# LCD_SD.net
KiCad netlist of a schematic drawn in Altium Designer
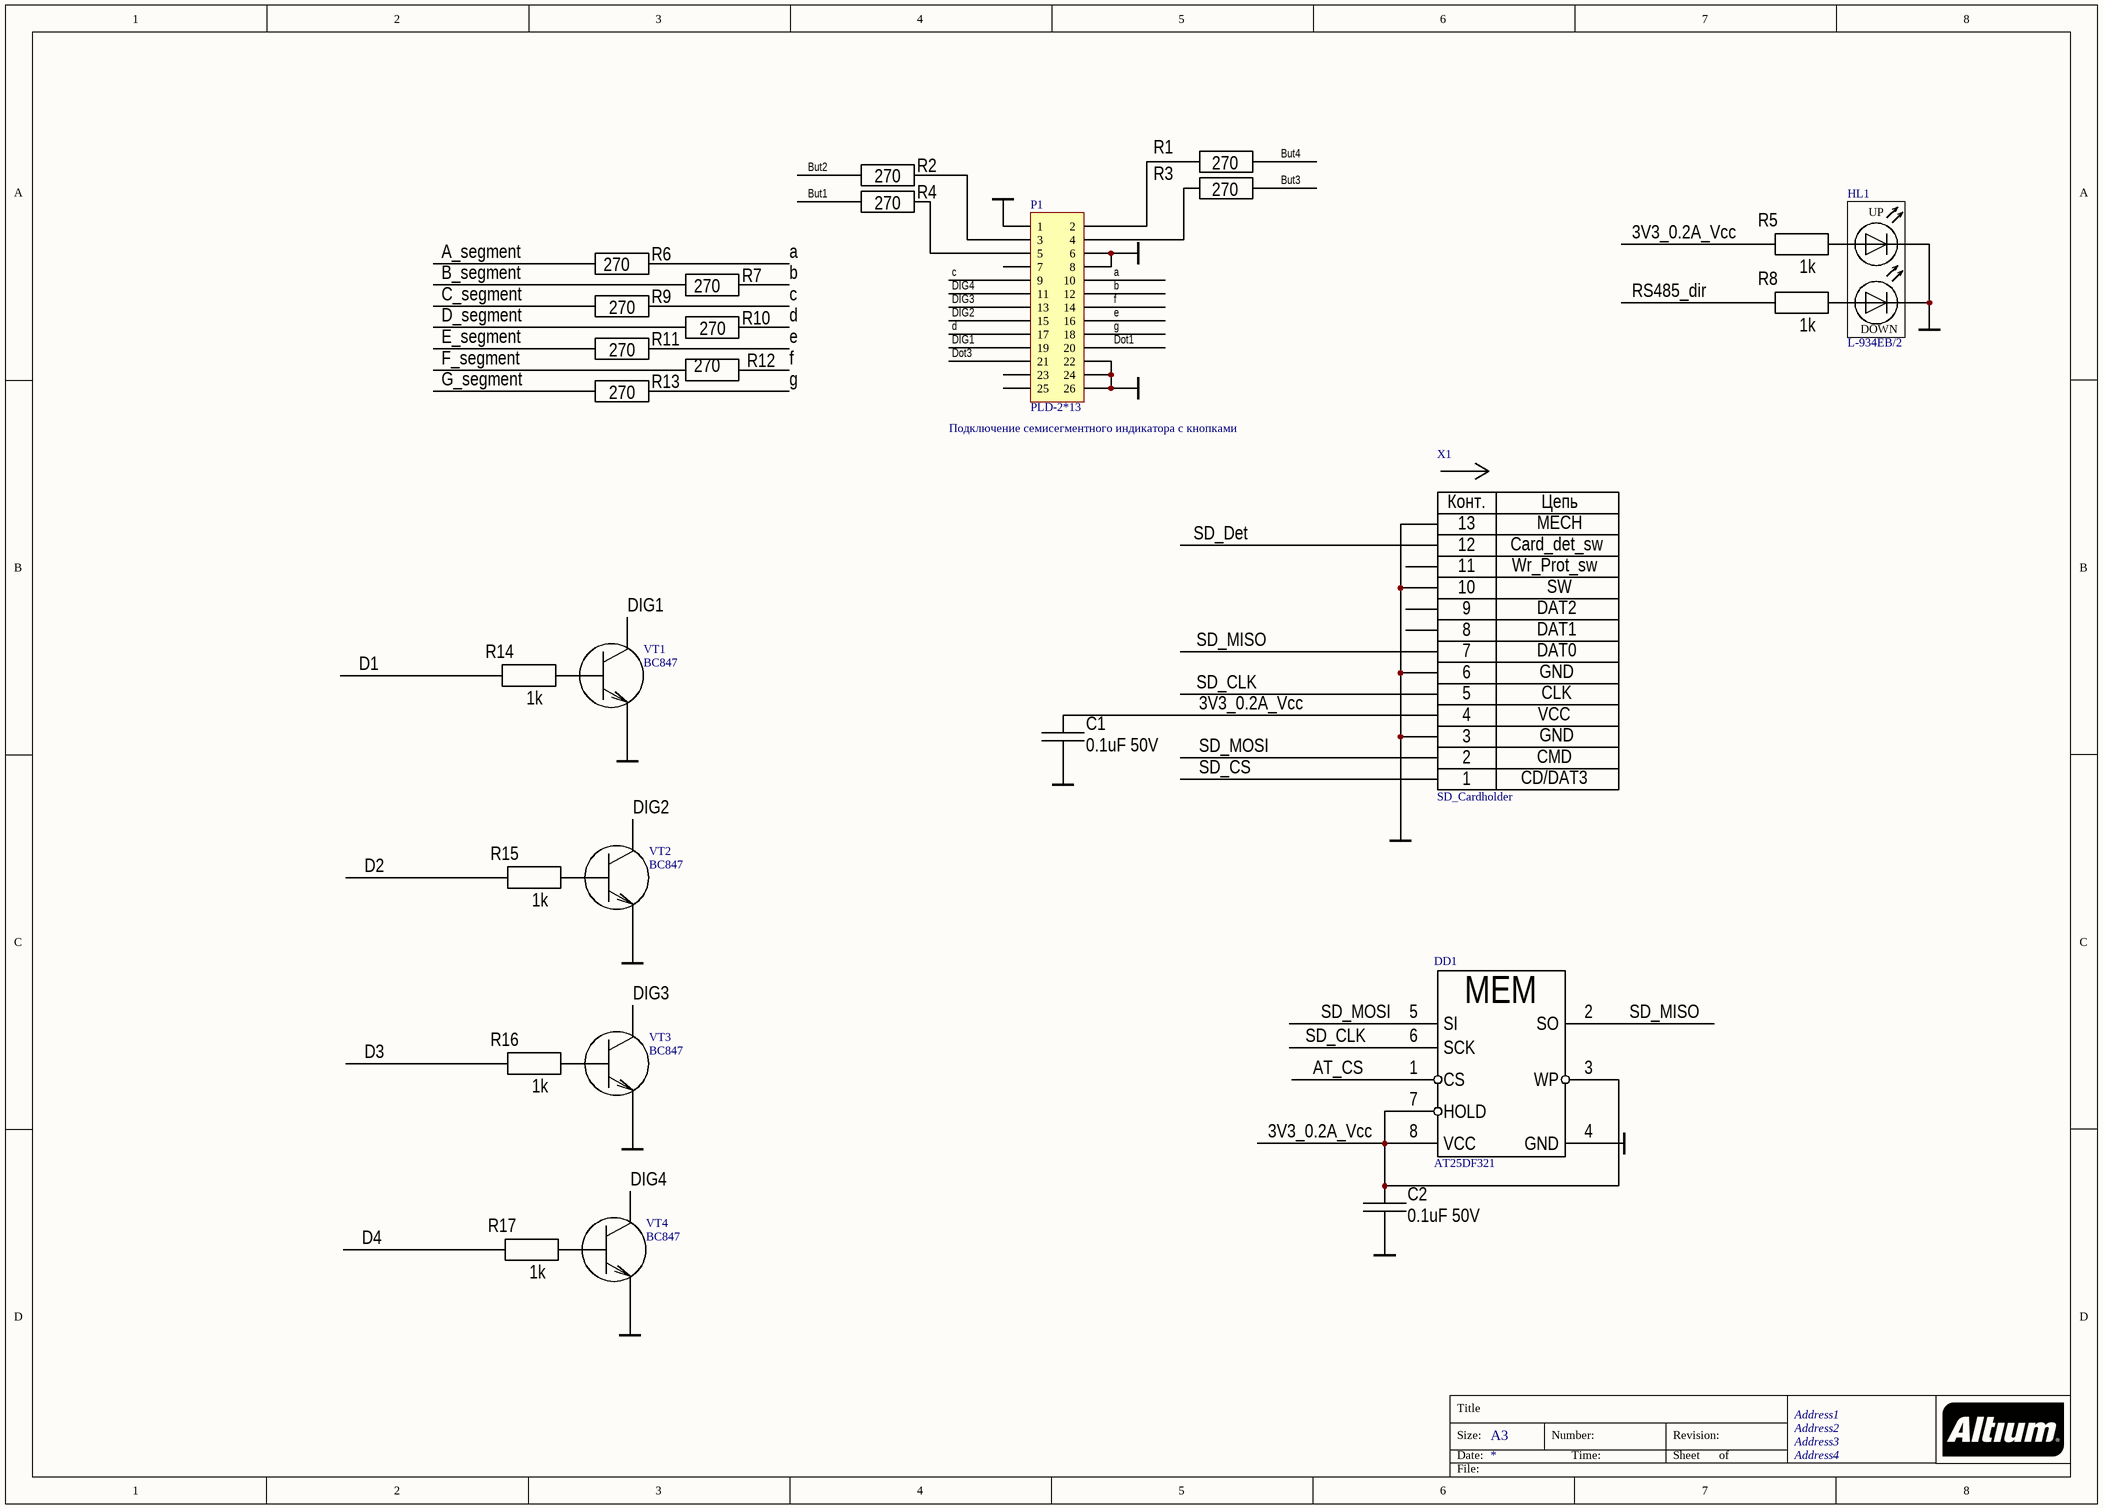
[diagram p0: LCD_SD.SchDoc]

(export (version "E")
  (design (tool "Eeschema 10.0.6"))
  (components
    (comp (ref "C1")
      (value "0.1uF 50V")
      (footprint "0805_CAP")
      (libsource (lib "Integrated_Library_tikhovikt") (part "Cap_np"))
    )
    (comp (ref "C2")
      (value "0.1uF 50V")
      (footprint "0805_CAP")
      (libsource (lib "Integrated_Library_tikhovikt") (part "Cap_np"))
    )
    (comp (ref "DD1")
      (value "AT25DF321")
      (footprint "soic8-200")
      (libsource (lib "Integrated_Library_tikhovikt") (part "AT25DF321"))
    )
    (comp (ref "HL1")
      (value "L-934EB/2")
      (footprint "L-934EB/2")
      (libsource (lib "Integrated_Library_tikhovikt") (part "LEDx2"))
    )
    (comp (ref "P1")
      (value "PLD-2*13")
      (footprint "HDR2X13")
      (description "Header, 13-Pin, Dual row")
      (fields (field (name "DESTINY") "Подключение семисегментного индикатора с кнопками"))
      (libsource (lib "Miscellaneous Connectors") (part "Header 13X2"))
    )
    (comp (ref "R1")
      (value "270")
      (footprint "0805_RES")
      (libsource (lib "Integrated_Library_tikhovikt") (part "Res"))
    )
    (comp (ref "R2")
      (value "270")
      (footprint "0805_RES")
      (libsource (lib "Integrated_Library_tikhovikt") (part "Res"))
    )
    (comp (ref "R3")
      (value "270")
      (footprint "0805_RES")
      (libsource (lib "Integrated_Library_tikhovikt") (part "Res"))
    )
    (comp (ref "R4")
      (value "270")
      (footprint "0805_RES")
      (libsource (lib "Integrated_Library_tikhovikt") (part "Res"))
    )
    (comp (ref "R5")
      (value "1k")
      (footprint "0805_RES")
      (libsource (lib "Integrated_Library_tikhovikt") (part "Res"))
    )
    (comp (ref "R6")
      (value "270")
      (footprint "0805_RES")
      (libsource (lib "Integrated_Library_tikhovikt") (part "Res"))
    )
    (comp (ref "R7")
      (value "270")
      (footprint "0805_RES")
      (libsource (lib "Integrated_Library_tikhovikt") (part "Res"))
    )
    (comp (ref "R8")
      (value "1k")
      (footprint "0805_RES")
      (libsource (lib "Integrated_Library_tikhovikt") (part "Res"))
    )
    (comp (ref "R9")
      (value "270")
      (footprint "0805_RES")
      (libsource (lib "Integrated_Library_tikhovikt") (part "Res"))
    )
    (comp (ref "R10")
      (value "270")
      (footprint "0805_RES")
      (libsource (lib "Integrated_Library_tikhovikt") (part "Res"))
    )
    (comp (ref "R11")
      (value "270")
      (footprint "0805_RES")
      (libsource (lib "Integrated_Library_tikhovikt") (part "Res"))
    )
    (comp (ref "R12")
      (value "270")
      (footprint "0805_RES")
      (libsource (lib "Integrated_Library_tikhovikt") (part "Res"))
    )
    (comp (ref "R13")
      (value "270")
      (footprint "0805_RES")
      (libsource (lib "Integrated_Library_tikhovikt") (part "Res"))
    )
    (comp (ref "R14")
      (value "1k")
      (footprint "0805_RES")
      (libsource (lib "Integrated_Library_tikhovikt") (part "Res"))
    )
    (comp (ref "R15")
      (value "1k")
      (footprint "0805_RES")
      (libsource (lib "Integrated_Library_tikhovikt") (part "Res"))
    )
    (comp (ref "R16")
      (value "1k")
      (footprint "0805_RES")
      (libsource (lib "Integrated_Library_tikhovikt") (part "Res"))
    )
    (comp (ref "R17")
      (value "1k")
      (footprint "0805_RES")
      (libsource (lib "Integrated_Library_tikhovikt") (part "Res"))
    )
    (comp (ref "VT1")
      (value "BC847")
      (footprint "sot23-3")
      (libsource (lib "Integrated_Library_tikhovikt") (part "transistor_npn"))
    )
    (comp (ref "VT2")
      (value "BC847")
      (footprint "sot23-3")
      (libsource (lib "Integrated_Library_tikhovikt") (part "transistor_npn"))
    )
    (comp (ref "VT3")
      (value "BC847")
      (footprint "sot23-3")
      (libsource (lib "Integrated_Library_tikhovikt") (part "transistor_npn"))
    )
    (comp (ref "VT4")
      (value "BC847")
      (footprint "sot23-3")
      (libsource (lib "Integrated_Library_tikhovikt") (part "transistor_npn"))
    )
    (comp (ref "X1")
      (value "SD_Cardholder")
      (footprint "SDcardHolder")
      (libsource (lib "Integrated_Library_tikhovikt") (part "SD_Cardholder"))
    )
  )
  (nets
    (net (code "1") (name "/3V3_0.2A_Vcc") (class "Default")
      (node (ref "C1") (pin "1") (pinfunction "1_1") (pintype "passive"))
      (node (ref "C2") (pin "1") (pinfunction "1_1") (pintype "passive"))
      (node (ref "DD1") (pin "3") (pinfunction "WP_3") (pintype "passive"))
      (node (ref "DD1") (pin "7") (pinfunction "HOLD_7") (pintype "passive"))
      (node (ref "DD1") (pin "8") (pinfunction "VCC_8") (pintype "passive"))
      (node (ref "R5") (pin "2") (pinfunction "2_2") (pintype "passive"))
      (node (ref "X1") (pin "4") (pinfunction "4_4") (pintype "passive"))
    )
    (net (code "2") (name "/AT_CS") (class "Default")
      (node (ref "DD1") (pin "1") (pinfunction "CS_1") (pintype "passive"))
    )
    (net (code "3") (name "/A_segment") (class "Default")
      (node (ref "R6") (pin "2") (pinfunction "2_2") (pintype "passive"))
    )
    (net (code "4") (name "/B_segment") (class "Default")
      (node (ref "R7") (pin "2") (pinfunction "2_2") (pintype "passive"))
    )
    (net (code "5") (name "/But1") (class "Default")
      (node (ref "R4") (pin "2") (pinfunction "2_2") (pintype "passive"))
    )
    (net (code "6") (name "/But2") (class "Default")
      (node (ref "R2") (pin "2") (pinfunction "2_2") (pintype "passive"))
    )
    (net (code "7") (name "/But3") (class "Default")
      (node (ref "R3") (pin "2") (pinfunction "2_2") (pintype "passive"))
    )
    (net (code "8") (name "/But4") (class "Default")
      (node (ref "R1") (pin "2") (pinfunction "2_2") (pintype "passive"))
    )
    (net (code "9") (name "/C_segment") (class "Default")
      (node (ref "R9") (pin "2") (pinfunction "2_2") (pintype "passive"))
    )
    (net (code "10") (name "/D1") (class "Default")
      (node (ref "R14") (pin "2") (pinfunction "2_2") (pintype "passive"))
    )
    (net (code "11") (name "/D2") (class "Default")
      (node (ref "R15") (pin "2") (pinfunction "2_2") (pintype "passive"))
    )
    (net (code "12") (name "/D3") (class "Default")
      (node (ref "R16") (pin "2") (pinfunction "2_2") (pintype "passive"))
    )
    (net (code "13") (name "/D4") (class "Default")
      (node (ref "R17") (pin "2") (pinfunction "2_2") (pintype "passive"))
    )
    (net (code "14") (name "/DIG1") (class "Default")
      (node (ref "P1") (pin "19") (pinfunction "19_19") (pintype "passive"))
      (node (ref "VT1") (pin "3") (pinfunction "C_3") (pintype "passive"))
    )
    (net (code "15") (name "/DIG2") (class "Default")
      (node (ref "P1") (pin "15") (pinfunction "15_15") (pintype "passive"))
      (node (ref "VT2") (pin "3") (pinfunction "C_3") (pintype "passive"))
    )
    (net (code "16") (name "/DIG3") (class "Default")
      (node (ref "P1") (pin "13") (pinfunction "13_13") (pintype "passive"))
      (node (ref "VT3") (pin "3") (pinfunction "C_3") (pintype "passive"))
    )
    (net (code "17") (name "/DIG4") (class "Default")
      (node (ref "P1") (pin "11") (pinfunction "11_11") (pintype "passive"))
      (node (ref "VT4") (pin "3") (pinfunction "C_3") (pintype "passive"))
    )
    (net (code "18") (name "/D_segment") (class "Default")
      (node (ref "R10") (pin "2") (pinfunction "2_2") (pintype "passive"))
    )
    (net (code "19") (name "/Dot1") (class "Default")
      (node (ref "P1") (pin "20") (pinfunction "20_20") (pintype "passive"))
    )
    (net (code "20") (name "/Dot3") (class "Default")
      (node (ref "P1") (pin "21") (pinfunction "21_21") (pintype "passive"))
    )
    (net (code "21") (name "/E_segment") (class "Default")
      (node (ref "R11") (pin "2") (pinfunction "2_2") (pintype "passive"))
    )
    (net (code "22") (name "/F_segment") (class "Default")
      (node (ref "R12") (pin "2") (pinfunction "2_2") (pintype "passive"))
    )
    (net (code "23") (name "/G_segment") (class "Default")
      (node (ref "R13") (pin "2") (pinfunction "2_2") (pintype "passive"))
    )
    (net (code "24") (name "/RS485_dir") (class "Default")
      (node (ref "R8") (pin "2") (pinfunction "2_2") (pintype "passive"))
    )
    (net (code "25") (name "/SD_CLK") (class "Default")
      (node (ref "DD1") (pin "6") (pinfunction "SCK_6") (pintype "passive"))
      (node (ref "X1") (pin "5") (pinfunction "5_5") (pintype "passive"))
    )
    (net (code "26") (name "/SD_CS") (class "Default")
      (node (ref "X1") (pin "1") (pinfunction "1_1") (pintype "passive"))
    )
    (net (code "27") (name "/SD_Det") (class "Default")
      (node (ref "X1") (pin "12") (pinfunction "12_12") (pintype "passive"))
    )
    (net (code "28") (name "/SD_MISO") (class "Default")
      (node (ref "DD1") (pin "2") (pinfunction "SO_2") (pintype "passive"))
      (node (ref "X1") (pin "7") (pinfunction "7_7") (pintype "passive"))
    )
    (net (code "29") (name "/SD_MOSI") (class "Default")
      (node (ref "DD1") (pin "5") (pinfunction "SI_5") (pintype "passive"))
      (node (ref "X1") (pin "2") (pinfunction "2_2") (pintype "passive"))
    )
    (net (code "30") (name "/a") (class "Default")
      (node (ref "P1") (pin "10") (pinfunction "10_10") (pintype "passive"))
      (node (ref "R6") (pin "1") (pinfunction "1_1") (pintype "passive"))
    )
    (net (code "31") (name "/b") (class "Default")
      (node (ref "P1") (pin "12") (pinfunction "12_12") (pintype "passive"))
      (node (ref "R7") (pin "1") (pinfunction "1_1") (pintype "passive"))
    )
    (net (code "32") (name "/c") (class "Default")
      (node (ref "P1") (pin "9") (pinfunction "9_9") (pintype "passive"))
      (node (ref "R9") (pin "1") (pinfunction "1_1") (pintype "passive"))
    )
    (net (code "33") (name "/d") (class "Default")
      (node (ref "P1") (pin "17") (pinfunction "17_17") (pintype "passive"))
      (node (ref "R10") (pin "1") (pinfunction "1_1") (pintype "passive"))
    )
    (net (code "34") (name "/e") (class "Default")
      (node (ref "P1") (pin "16") (pinfunction "16_16") (pintype "passive"))
      (node (ref "R11") (pin "1") (pinfunction "1_1") (pintype "passive"))
    )
    (net (code "35") (name "/f") (class "Default")
      (node (ref "P1") (pin "14") (pinfunction "14_14") (pintype "passive"))
      (node (ref "R12") (pin "1") (pinfunction "1_1") (pintype "passive"))
    )
    (net (code "36") (name "/g") (class "Default")
      (node (ref "P1") (pin "18") (pinfunction "18_18") (pintype "passive"))
      (node (ref "R13") (pin "1") (pinfunction "1_1") (pintype "passive"))
    )
    (net (code "37") (name "GND") (class "Default")
      (node (ref "C1") (pin "2") (pinfunction "2_2") (pintype "passive"))
      (node (ref "C2") (pin "2") (pinfunction "2_2") (pintype "passive"))
      (node (ref "DD1") (pin "4") (pinfunction "GND_4") (pintype "passive"))
      (node (ref "HL1") (pin "1") (pinfunction "1_1") (pintype "passive"))
      (node (ref "HL1") (pin "3") (pinfunction "3_3") (pintype "passive"))
      (node (ref "P1") (pin "1") (pinfunction "1_1") (pintype "passive"))
      (node (ref "P1") (pin "22") (pinfunction "22_22") (pintype "passive"))
      (node (ref "P1") (pin "24") (pinfunction "24_24") (pintype "passive"))
      (node (ref "P1") (pin "26") (pinfunction "26_26") (pintype "passive"))
      (node (ref "P1") (pin "6") (pinfunction "6_6") (pintype "passive"))
      (node (ref "P1") (pin "8") (pinfunction "8_8") (pintype "passive"))
      (node (ref "VT1") (pin "2") (pinfunction "E_2") (pintype "passive"))
      (node (ref "VT2") (pin "2") (pinfunction "E_2") (pintype "passive"))
      (node (ref "VT3") (pin "2") (pinfunction "E_2") (pintype "passive"))
      (node (ref "VT4") (pin "2") (pinfunction "E_2") (pintype "passive"))
      (node (ref "X1") (pin "10") (pinfunction "10_10") (pintype "passive"))
      (node (ref "X1") (pin "13") (pinfunction "13_13") (pintype "passive"))
      (node (ref "X1") (pin "3") (pinfunction "3_3") (pintype "passive"))
      (node (ref "X1") (pin "6") (pinfunction "6_6") (pintype "passive"))
    )
    (net (code "38") (name "Net-(HL1-Pad2)") (class "Default")
      (node (ref "HL1") (pin "2") (pinfunction "2_2") (pintype "passive"))
      (node (ref "R8") (pin "1") (pinfunction "1_1") (pintype "passive"))
    )
    (net (code "39") (name "Net-(HL1-Pad4)") (class "Default")
      (node (ref "HL1") (pin "4") (pinfunction "4_4") (pintype "passive"))
      (node (ref "R5") (pin "1") (pinfunction "1_1") (pintype "passive"))
    )
    (net (code "40") (name "Net-(P1-Pad2)") (class "Default")
      (node (ref "P1") (pin "2") (pinfunction "2_2") (pintype "passive"))
      (node (ref "R1") (pin "1") (pinfunction "1_1") (pintype "passive"))
    )
    (net (code "41") (name "Net-(P1-Pad3)") (class "Default")
      (node (ref "P1") (pin "3") (pinfunction "3_3") (pintype "passive"))
      (node (ref "R2") (pin "1") (pinfunction "1_1") (pintype "passive"))
    )
    (net (code "42") (name "Net-(P1-Pad4)") (class "Default")
      (node (ref "P1") (pin "4") (pinfunction "4_4") (pintype "passive"))
      (node (ref "R3") (pin "1") (pinfunction "1_1") (pintype "passive"))
    )
    (net (code "43") (name "Net-(P1-Pad5)") (class "Default")
      (node (ref "P1") (pin "5") (pinfunction "5_5") (pintype "passive"))
      (node (ref "R4") (pin "1") (pinfunction "1_1") (pintype "passive"))
    )
    (net (code "44") (name "Net-(VT1-B)") (class "Default")
      (node (ref "R14") (pin "1") (pinfunction "1_1") (pintype "passive"))
      (node (ref "VT1") (pin "1") (pinfunction "B_1") (pintype "passive"))
    )
    (net (code "45") (name "Net-(VT2-B)") (class "Default")
      (node (ref "R15") (pin "1") (pinfunction "1_1") (pintype "passive"))
      (node (ref "VT2") (pin "1") (pinfunction "B_1") (pintype "passive"))
    )
    (net (code "46") (name "Net-(VT3-B)") (class "Default")
      (node (ref "R16") (pin "1") (pinfunction "1_1") (pintype "passive"))
      (node (ref "VT3") (pin "1") (pinfunction "B_1") (pintype "passive"))
    )
    (net (code "47") (name "Net-(VT4-B)") (class "Default")
      (node (ref "R17") (pin "1") (pinfunction "1_1") (pintype "passive"))
      (node (ref "VT4") (pin "1") (pinfunction "B_1") (pintype "passive"))
    )
    (net (code "48") (name "unconnected-(P1-Pad7)") (class "Default")
      (node (ref "P1") (pin "7") (pinfunction "7_7") (pintype "passive"))
    )
    (net (code "49") (name "unconnected-(P1-Pad23)") (class "Default")
      (node (ref "P1") (pin "23") (pinfunction "23_23") (pintype "passive"))
    )
    (net (code "50") (name "unconnected-(P1-Pad25)") (class "Default")
      (node (ref "P1") (pin "25") (pinfunction "25_25") (pintype "passive"))
    )
    (net (code "51") (name "unconnected-(X1-Pad8)") (class "Default")
      (node (ref "X1") (pin "8") (pinfunction "8_8") (pintype "passive"))
    )
    (net (code "52") (name "unconnected-(X1-Pad9)") (class "Default")
      (node (ref "X1") (pin "9") (pinfunction "9_9") (pintype "passive"))
    )
    (net (code "53") (name "unconnected-(X1-Pad11)") (class "Default")
      (node (ref "X1") (pin "11") (pinfunction "11_11") (pintype "passive"))
    )
  )
)
